# CH340C9T-R0.net
KiCad netlist of a schematic drawn in Altium Designer
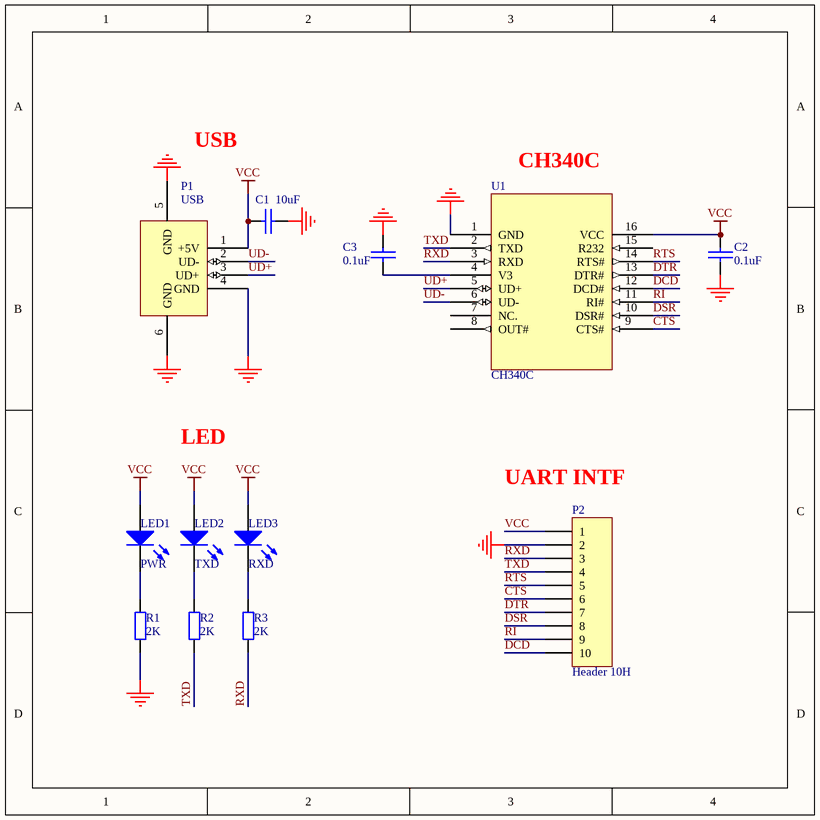
[diagram p0: CH340C9T-R0.SchDoc]

(export (version "E")
  (design (tool "Eeschema 10.0.6"))
  (components
    (comp (ref "C1")
      (value "10uF")
      (footprint "3216_C")
      (description "Capacitor")
      (libsource (lib "*") (part "CAP"))
    )
    (comp (ref "C2")
      (value "0.1uF")
      (footprint "0603_C")
      (description "Capacitor")
      (libsource (lib "*") (part "CAP"))
    )
    (comp (ref "C3")
      (value "0.1uF")
      (footprint "0603_C")
      (description "Capacitor")
      (libsource (lib "*") (part "CAP"))
    )
    (comp (ref "LED1")
      (value "PWR")
      (footprint "0603+")
      (description "Typical RED, GREEN, YELLOW, AMBER GaAs LED")
      (libsource (lib "*") (part "LED2"))
    )
    (comp (ref "LED2")
      (value "TXD")
      (footprint "0603+")
      (description "Typical RED, GREEN, YELLOW, AMBER GaAs LED")
      (libsource (lib "*") (part "LED2"))
    )
    (comp (ref "LED3")
      (value "RXD")
      (footprint "0603+")
      (description "Typical RED, GREEN, YELLOW, AMBER GaAs LED")
      (libsource (lib "*") (part "LED2"))
    )
    (comp (ref "P1") (value "USB") (footprint "USBAM") (libsource (lib "*") (part "USB")))
    (comp (ref "P2")
      (value "Header 10H")
      (footprint "SIP10-2.54mm")
      (description "Header, 10-Pin, Right Angle")
      (fields (field (name "PUBLISHER") "Altium Limited"))
      (libsource (lib "Miscellaneous Connectors") (part "Header 10H"))
    )
    (comp (ref "R1")
      (value "2K")
      (footprint "0603")
      (description "Resistor")
      (libsource (lib "*") (part "Res2"))
    )
    (comp (ref "R2")
      (value "2K")
      (footprint "0603")
      (description "Resistor")
      (libsource (lib "*") (part "Res2"))
    )
    (comp (ref "R3")
      (value "2K")
      (footprint "0603")
      (description "Resistor")
      (libsource (lib "*") (part "Res2"))
    )
    (comp (ref "U1")
      (value "CH340C")
      (footprint "SOP16")
      (description "USB to TTL Serial / UART")
      (libsource (lib "CHXXXSCH") (part "CH340C"))
    )
  )
  (nets
    (net (code "1") (name "/CTS") (class "Default")
      (node (ref "P2") (pin "6") (pinfunction "6_6") (pintype "passive"))
      (node (ref "U1") (pin "9") (pinfunction "CTS#_9") (pintype "input"))
    )
    (net (code "2") (name "/DCD") (class "Default")
      (node (ref "P2") (pin "10") (pinfunction "10_10") (pintype "passive"))
      (node (ref "U1") (pin "12") (pinfunction "DCD#_12") (pintype "input"))
    )
    (net (code "3") (name "/DSR") (class "Default")
      (node (ref "P2") (pin "8") (pinfunction "8_8") (pintype "passive"))
      (node (ref "U1") (pin "10") (pinfunction "DSR#_10") (pintype "input"))
    )
    (net (code "4") (name "/DTR") (class "Default")
      (node (ref "P2") (pin "7") (pinfunction "7_7") (pintype "passive"))
      (node (ref "U1") (pin "13") (pinfunction "DTR#_13") (pintype "output"))
    )
    (net (code "5") (name "/RI") (class "Default")
      (node (ref "P2") (pin "9") (pinfunction "9_9") (pintype "passive"))
      (node (ref "U1") (pin "11") (pinfunction "RI#_11") (pintype "input"))
    )
    (net (code "6") (name "/RTS") (class "Default")
      (node (ref "P2") (pin "5") (pinfunction "5_5") (pintype "passive"))
      (node (ref "U1") (pin "14") (pinfunction "RTS#_14") (pintype "output"))
    )
    (net (code "7") (name "/RXD") (class "Default")
      (node (ref "P2") (pin "3") (pinfunction "3_3") (pintype "passive"))
      (node (ref "R3") (pin "2") (pinfunction "2_2") (pintype "passive"))
      (node (ref "U1") (pin "3") (pinfunction "RXD_3") (pintype "input"))
    )
    (net (code "8") (name "/TXD") (class "Default")
      (node (ref "P2") (pin "4") (pinfunction "4_4") (pintype "passive"))
      (node (ref "R2") (pin "2") (pinfunction "2_2") (pintype "passive"))
      (node (ref "U1") (pin "2") (pinfunction "TXD_2") (pintype "output"))
    )
    (net (code "9") (name "/UD+") (class "Default")
      (node (ref "P1") (pin "3") (pinfunction "UD+_3") (pintype "bidirectional"))
      (node (ref "U1") (pin "5") (pinfunction "UD+_5") (pintype "bidirectional"))
    )
    (net (code "10") (name "/UD-") (class "Default")
      (node (ref "P1") (pin "2") (pinfunction "UD-_2") (pintype "bidirectional"))
      (node (ref "U1") (pin "6") (pinfunction "UD-_6") (pintype "bidirectional"))
    )
    (net (code "11") (name "GND") (class "Default")
      (node (ref "C1") (pin "2") (pinfunction "2_2") (pintype "passive"))
      (node (ref "C2") (pin "2") (pinfunction "2_2") (pintype "passive"))
      (node (ref "C3") (pin "2") (pinfunction "2_2") (pintype "passive"))
      (node (ref "P1") (pin "4") (pinfunction "GND_4") (pintype "power_in"))
      (node (ref "P1") (pin "5") (pinfunction "GND_5") (pintype "power_in"))
      (node (ref "P1") (pin "6") (pinfunction "GND_6") (pintype "power_in"))
      (node (ref "P2") (pin "2") (pinfunction "2_2") (pintype "passive"))
      (node (ref "R1") (pin "2") (pinfunction "2_2") (pintype "passive"))
      (node (ref "U1") (pin "1") (pinfunction "GND_1") (pintype "power_in"))
    )
    (net (code "12") (name "Net-(LED1-K)") (class "Default")
      (node (ref "LED1") (pin "2") (pinfunction "K_2") (pintype "passive"))
      (node (ref "R1") (pin "1") (pinfunction "1_1") (pintype "passive"))
    )
    (net (code "13") (name "Net-(LED2-K)") (class "Default")
      (node (ref "LED2") (pin "2") (pinfunction "K_2") (pintype "passive"))
      (node (ref "R2") (pin "1") (pinfunction "1_1") (pintype "passive"))
    )
    (net (code "14") (name "Net-(LED3-K)") (class "Default")
      (node (ref "LED3") (pin "2") (pinfunction "K_2") (pintype "passive"))
      (node (ref "R3") (pin "1") (pinfunction "1_1") (pintype "passive"))
    )
    (net (code "15") (name "Net-(U1-V3)") (class "Default")
      (node (ref "C3") (pin "1") (pinfunction "1_1") (pintype "passive"))
      (node (ref "U1") (pin "4") (pinfunction "V3_4") (pintype "power_in"))
    )
    (net (code "16") (name "VCC") (class "Default")
      (node (ref "C1") (pin "1") (pinfunction "1_1") (pintype "passive"))
      (node (ref "C2") (pin "1") (pinfunction "1_1") (pintype "passive"))
      (node (ref "LED1") (pin "1") (pinfunction "A_1") (pintype "passive"))
      (node (ref "LED2") (pin "1") (pinfunction "A_1") (pintype "passive"))
      (node (ref "LED3") (pin "1") (pinfunction "A_1") (pintype "passive"))
      (node (ref "P1") (pin "1") (pinfunction "+5V_1") (pintype "power_in"))
      (node (ref "P2") (pin "1") (pinfunction "1_1") (pintype "passive"))
      (node (ref "U1") (pin "16") (pinfunction "VCC_16") (pintype "power_in"))
    )
    (net (code "17") (name "unconnected-(U1-NC.-Pad7)") (class "Default")
      (node (ref "U1") (pin "7") (pinfunction "NC._7") (pintype "passive"))
    )
    (net (code "18") (name "unconnected-(U1-OUT#-Pad8)") (class "Default")
      (node (ref "U1") (pin "8") (pinfunction "OUT#_8") (pintype "output"))
    )
    (net (code "19") (name "unconnected-(U1-R232-Pad15)") (class "Default")
      (node (ref "U1") (pin "15") (pinfunction "R232_15") (pintype "input"))
    )
  )
)
